# Preliminary_Schematic.net
KiCad netlist of a schematic drawn in EAGLE
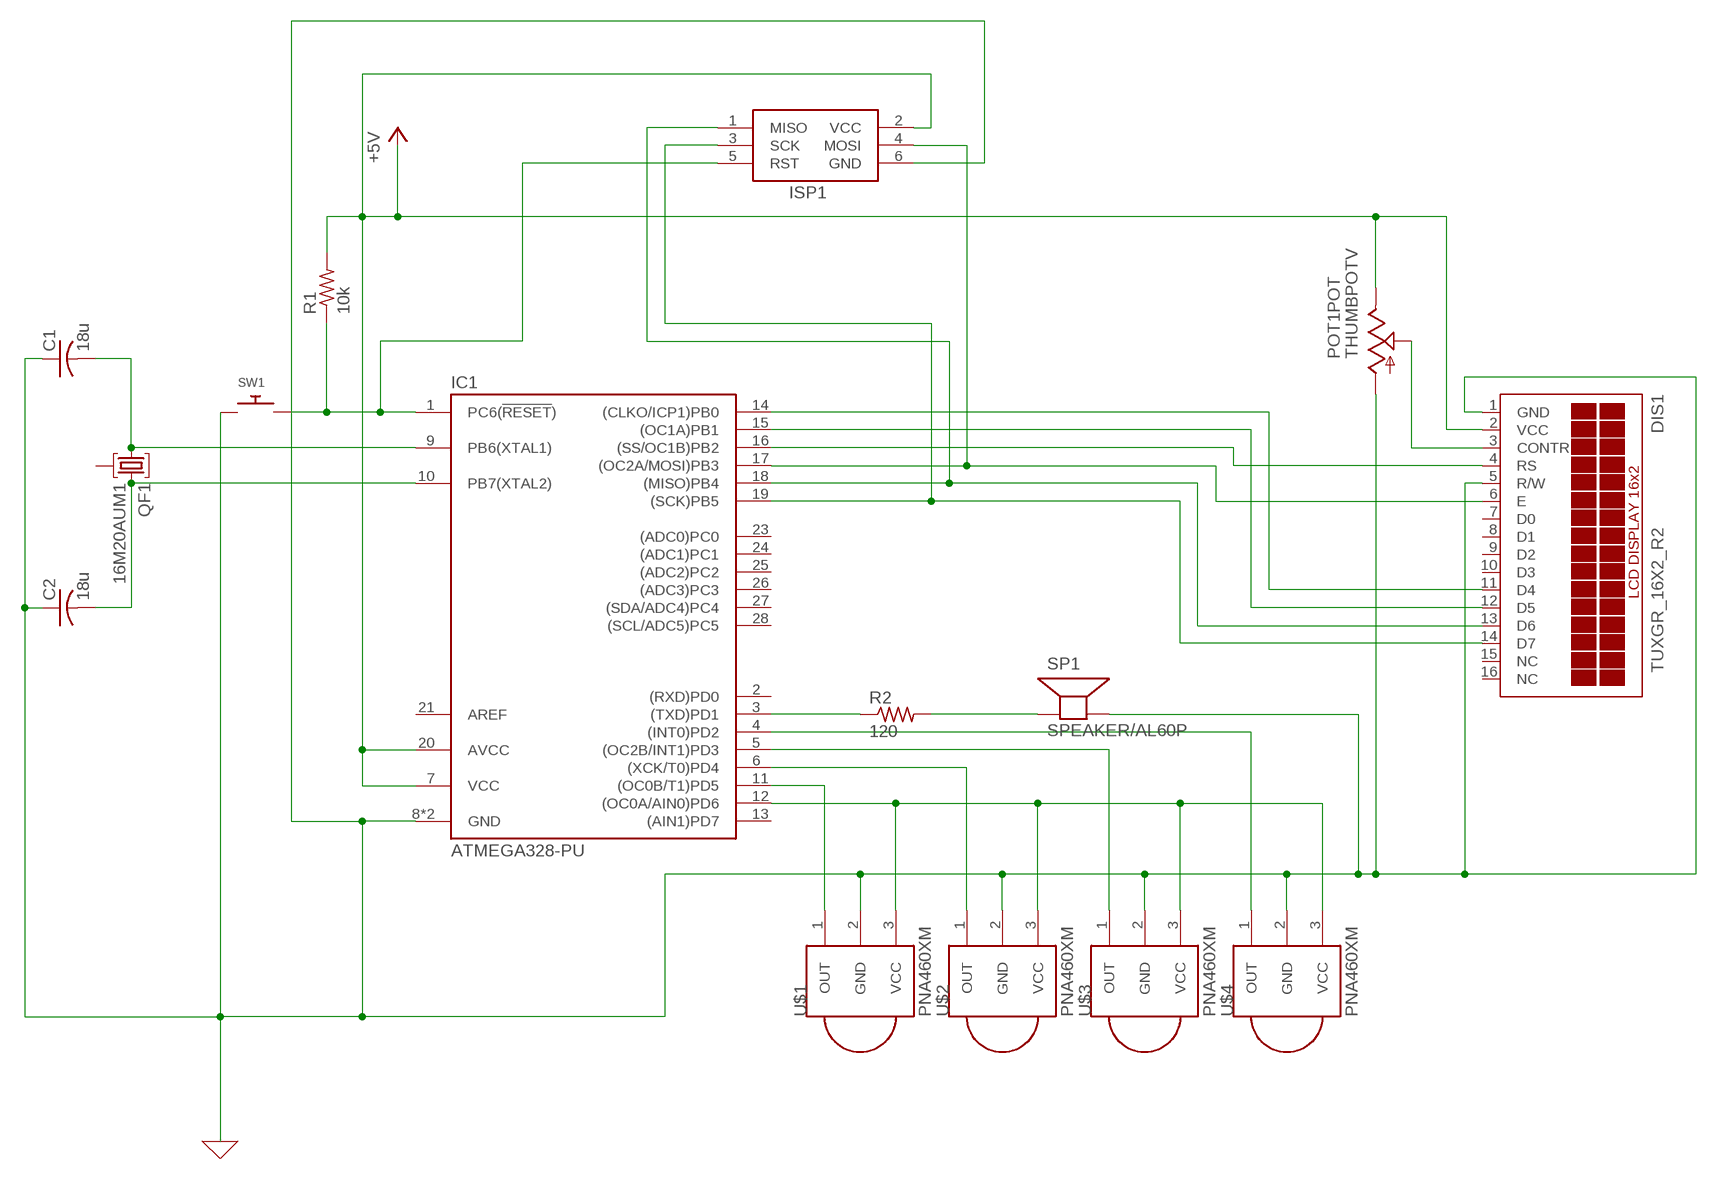
[diagram p0: schematic, sheet 1]

(export (version "E")
  (design (tool "Eeschema 10.0.6"))
  (components
    (comp (ref "C1")
      (value "18u")
      (footprint "eagle-import:C0805")
      (libsource (lib "eagle-import") (part "C-USC0805"))
    )
    (comp (ref "C2")
      (value "18u")
      (footprint "eagle-import:C0805")
      (libsource (lib "eagle-import") (part "C-USC0805"))
    )
    (comp (ref "DIS1")
      (value "TUXGR_16X2_R2")
      (footprint "eagle-import:TUXGR_16X2_R2")
      (libsource (lib "eagle-import") (part "TUXGR_16X2_R2"))
    )
    (comp (ref "IC1")
      (value "ATMEGA328-PU")
      (footprint "eagle-import:DIL28")
      (fields (field (name "MF") "Microchip"))
      (libsource (lib "eagle-import") (part "ATMEGA328-PU"))
    )
    (comp (ref "ISP1")
      (value "AVRISP-6")
      (footprint "eagle-import:AVRISP")
      (libsource (lib "eagle-import") (part "AVRISP-6"))
    )
    (comp (ref "POT1")
      (value "THUMBPOTV")
      (footprint "eagle-import:THUMBWHEELV")
      (libsource (lib "eagle-import") (part "THUMBPOTV"))
    )
    (comp (ref "QF1")
      (value "16M20AUM1")
      (footprint "eagle-import:UM1")
      (libsource (lib "eagle-import") (part "16M20AUM1"))
    )
    (comp (ref "R1")
      (value "10k")
      (footprint "eagle-import:R0805")
      (libsource (lib "eagle-import") (part "R-US_R0805"))
    )
    (comp (ref "R2")
      (value "120")
      (footprint "eagle-import:R0805")
      (libsource (lib "eagle-import") (part "R-US_R0805"))
    )
    (comp (ref "SP1")
      (value "SPEAKER/AL60P")
      (footprint "eagle-import:AL60P")
      (libsource (lib "eagle-import") (part "SPEAKER/AL60P"))
    )
    (comp (ref "SW1")
      (value "SWITCH_PUSHBUTTONC&K_KSS")
      (footprint "eagle-import:BTN_CK_KSS")
      (libsource (lib "eagle-import") (part "SWITCH_PUSHBUTTONC&K_KSS"))
    )
    (comp (ref "U$1")
      (value "PNA460XM")
      (footprint "eagle-import:PNA460XM")
      (libsource (lib "eagle-import") (part "PNA460XM"))
    )
    (comp (ref "U$2")
      (value "PNA460XM")
      (footprint "eagle-import:PNA460XM")
      (libsource (lib "eagle-import") (part "PNA460XM"))
    )
    (comp (ref "U$3")
      (value "PNA460XM")
      (footprint "eagle-import:PNA460XM")
      (libsource (lib "eagle-import") (part "PNA460XM"))
    )
    (comp (ref "U$4")
      (value "PNA460XM")
      (footprint "eagle-import:PNA460XM")
      (libsource (lib "eagle-import") (part "PNA460XM"))
    )
  )
  (nets
    (net (code "1") (name "+5V") (class "Default")
      (node (ref "DIS1") (pin "2") (pinfunction "VCC_2") (pintype "power_in"))
      (node (ref "IC1") (pin "20") (pinfunction "AVCC_20") (pintype "power_in"))
      (node (ref "IC1") (pin "7") (pinfunction "VCC_7") (pintype "power_in"))
      (node (ref "ISP1") (pin "2") (pinfunction "VCC_2") (pintype "power_in"))
      (node (ref "POT1") (pin "E") (pinfunction "E_E") (pintype "passive"))
      (node (ref "R1") (pin "2") (pinfunction "2_2") (pintype "passive"))
    )
    (net (code "2") (name "GND") (class "Default")
      (node (ref "C1") (pin "1") (pinfunction "1_1") (pintype "passive"))
      (node (ref "C2") (pin "1") (pinfunction "1_1") (pintype "passive"))
      (node (ref "DIS1") (pin "1") (pinfunction "GND_1") (pintype "power_in"))
      (node (ref "DIS1") (pin "5") (pinfunction "R/W_5") (pintype "input"))
      (node (ref "IC1") (pin "22") (pinfunction "GND_22") (pintype "power_in"))
      (node (ref "IC1") (pin "8") (pinfunction "GND_8") (pintype "power_in"))
      (node (ref "ISP1") (pin "6") (pinfunction "GND_6") (pintype "power_in"))
      (node (ref "POT1") (pin "A") (pinfunction "A_A") (pintype "passive"))
      (node (ref "SP1") (pin "2") (pinfunction "-_2") (pintype "passive"))
      (node (ref "SW1") (pin "P$1") (pinfunction "P$1_P$1") (pintype "passive"))
      (node (ref "U$1") (pin "2") (pinfunction "GND_2") (pintype "power_in"))
      (node (ref "U$2") (pin "2") (pinfunction "GND_2") (pintype "power_in"))
      (node (ref "U$3") (pin "2") (pinfunction "GND_2") (pintype "power_in"))
      (node (ref "U$4") (pin "2") (pinfunction "GND_2") (pintype "power_in"))
    )
    (net (code "3") (name "Net-(DIS1-CONTR)") (class "Default")
      (node (ref "DIS1") (pin "3") (pinfunction "CONTR_3") (pintype "input"))
      (node (ref "POT1") (pin "S") (pinfunction "S_S") (pintype "passive"))
    )
    (net (code "4") (name "Net-(DIS1-D4)") (class "Default")
      (node (ref "DIS1") (pin "11") (pinfunction "D4_11") (pintype "input"))
      (node (ref "IC1") (pin "14") (pinfunction "(CLKO/ICP1)PB0_14") (pintype "bidirectional"))
    )
    (net (code "5") (name "Net-(DIS1-D5)") (class "Default")
      (node (ref "DIS1") (pin "12") (pinfunction "D5_12") (pintype "input"))
      (node (ref "IC1") (pin "15") (pinfunction "(OC1A)PB1_15") (pintype "bidirectional"))
    )
    (net (code "6") (name "Net-(DIS1-D6)") (class "Default")
      (node (ref "DIS1") (pin "13") (pinfunction "D6_13") (pintype "input"))
      (node (ref "IC1") (pin "18") (pinfunction "(MISO)PB4_18") (pintype "bidirectional"))
      (node (ref "ISP1") (pin "1") (pinfunction "MISO_1") (pintype "input"))
    )
    (net (code "7") (name "Net-(DIS1-D7)") (class "Default")
      (node (ref "DIS1") (pin "14") (pinfunction "D7_14") (pintype "input"))
      (node (ref "IC1") (pin "19") (pinfunction "(SCK)PB5_19") (pintype "bidirectional"))
      (node (ref "ISP1") (pin "3") (pinfunction "SCK_3") (pintype "output"))
    )
    (net (code "8") (name "Net-(DIS1-E)") (class "Default")
      (node (ref "DIS1") (pin "6") (pinfunction "E_6") (pintype "input"))
      (node (ref "IC1") (pin "17") (pinfunction "(OC2A/MOSI)PB3_17") (pintype "bidirectional"))
      (node (ref "ISP1") (pin "4") (pinfunction "MOSI_4") (pintype "output"))
    )
    (net (code "9") (name "Net-(DIS1-RS)") (class "Default")
      (node (ref "DIS1") (pin "4") (pinfunction "RS_4") (pintype "input"))
      (node (ref "IC1") (pin "16") (pinfunction "(SS/OC1B)PB2_16") (pintype "bidirectional"))
    )
    (net (code "10") (name "Net-(IC1-(INT0)PD2)") (class "Default")
      (node (ref "IC1") (pin "4") (pinfunction "(INT0)PD2_4") (pintype "bidirectional"))
      (node (ref "U$4") (pin "1") (pinfunction "OUT_1") (pintype "output"))
    )
    (net (code "11") (name "Net-(IC1-(OC0A{slash}AIN0)PD6)") (class "Default")
      (node (ref "IC1") (pin "12") (pinfunction "(OC0A/AIN0)PD6_12") (pintype "bidirectional"))
      (node (ref "U$1") (pin "3") (pinfunction "VCC_3") (pintype "power_in"))
      (node (ref "U$2") (pin "3") (pinfunction "VCC_3") (pintype "power_in"))
      (node (ref "U$3") (pin "3") (pinfunction "VCC_3") (pintype "power_in"))
      (node (ref "U$4") (pin "3") (pinfunction "VCC_3") (pintype "power_in"))
    )
    (net (code "12") (name "Net-(IC1-(OC0B{slash}T1)PD5)") (class "Default")
      (node (ref "IC1") (pin "11") (pinfunction "(OC0B/T1)PD5_11") (pintype "bidirectional"))
      (node (ref "U$1") (pin "1") (pinfunction "OUT_1") (pintype "output"))
    )
    (net (code "13") (name "Net-(IC1-(OC2B{slash}INT1)PD3)") (class "Default")
      (node (ref "IC1") (pin "5") (pinfunction "(OC2B/INT1)PD3_5") (pintype "bidirectional"))
      (node (ref "U$3") (pin "1") (pinfunction "OUT_1") (pintype "output"))
    )
    (net (code "14") (name "Net-(IC1-(TXD)PD1)") (class "Default")
      (node (ref "IC1") (pin "3") (pinfunction "(TXD)PD1_3") (pintype "bidirectional"))
      (node (ref "R2") (pin "1") (pinfunction "1_1") (pintype "passive"))
    )
    (net (code "15") (name "Net-(IC1-(XCK{slash}T0)PD4)") (class "Default")
      (node (ref "IC1") (pin "6") (pinfunction "(XCK/T0)PD4_6") (pintype "bidirectional"))
      (node (ref "U$2") (pin "1") (pinfunction "OUT_1") (pintype "output"))
    )
    (net (code "16") (name "Net-(IC1-PB6(XTAL1))") (class "Default")
      (node (ref "C1") (pin "2") (pinfunction "2_2") (pintype "passive"))
      (node (ref "IC1") (pin "9") (pinfunction "PB6(XTAL1)_9") (pintype "bidirectional"))
      (node (ref "QF1") (pin "1") (pinfunction "1_1") (pintype "passive"))
    )
    (net (code "17") (name "Net-(IC1-PB7(XTAL2))") (class "Default")
      (node (ref "C2") (pin "2") (pinfunction "2_2") (pintype "passive"))
      (node (ref "IC1") (pin "10") (pinfunction "PB7(XTAL2)_10") (pintype "bidirectional"))
      (node (ref "QF1") (pin "3") (pinfunction "3_3") (pintype "passive"))
    )
    (net (code "18") (name "Net-(IC1-PC6(~{RESET}))") (class "Default")
      (node (ref "IC1") (pin "1") (pinfunction "PC6(~{RESET})_1") (pintype "bidirectional"))
      (node (ref "ISP1") (pin "5") (pinfunction "RST_5") (pintype "output"))
      (node (ref "R1") (pin "1") (pinfunction "1_1") (pintype "passive"))
      (node (ref "SW1") (pin "P$2") (pinfunction "P$2_P$2") (pintype "passive"))
    )
    (net (code "19") (name "Net-(SP1-+)") (class "Default")
      (node (ref "R2") (pin "2") (pinfunction "2_2") (pintype "passive"))
      (node (ref "SP1") (pin "1") (pinfunction "+_1") (pintype "passive"))
    )
    (net (code "20") (name "unconnected-(DIS1-D0-Pad7)") (class "Default")
      (node (ref "DIS1") (pin "7") (pinfunction "D0_7") (pintype "input"))
    )
    (net (code "21") (name "unconnected-(DIS1-D1-Pad8)") (class "Default")
      (node (ref "DIS1") (pin "8") (pinfunction "D1_8") (pintype "input"))
    )
    (net (code "22") (name "unconnected-(DIS1-D2-Pad9)") (class "Default")
      (node (ref "DIS1") (pin "9") (pinfunction "D2_9") (pintype "input"))
    )
    (net (code "23") (name "unconnected-(DIS1-D3-Pad10)") (class "Default")
      (node (ref "DIS1") (pin "10") (pinfunction "D3_10") (pintype "input"))
    )
    (net (code "24") (name "unconnected-(DIS1-NC-Pad15)") (class "Default")
      (node (ref "DIS1") (pin "15") (pinfunction "NC_15") (pintype "no_connect"))
    )
    (net (code "25") (name "unconnected-(DIS1-NC-Pad16)") (class "Default")
      (node (ref "DIS1") (pin "16") (pinfunction "NC_16") (pintype "no_connect"))
    )
    (net (code "26") (name "unconnected-(IC1-(ADC0)PC0-Pad23)") (class "Default")
      (node (ref "IC1") (pin "23") (pinfunction "(ADC0)PC0_23") (pintype "bidirectional"))
    )
    (net (code "27") (name "unconnected-(IC1-(ADC1)PC1-Pad24)") (class "Default")
      (node (ref "IC1") (pin "24") (pinfunction "(ADC1)PC1_24") (pintype "bidirectional"))
    )
    (net (code "28") (name "unconnected-(IC1-(ADC2)PC2-Pad25)") (class "Default")
      (node (ref "IC1") (pin "25") (pinfunction "(ADC2)PC2_25") (pintype "bidirectional"))
    )
    (net (code "29") (name "unconnected-(IC1-(ADC3)PC3-Pad26)") (class "Default")
      (node (ref "IC1") (pin "26") (pinfunction "(ADC3)PC3_26") (pintype "bidirectional"))
    )
    (net (code "30") (name "unconnected-(IC1-(AIN1)PD7-Pad13)") (class "Default")
      (node (ref "IC1") (pin "13") (pinfunction "(AIN1)PD7_13") (pintype "bidirectional"))
    )
    (net (code "31") (name "unconnected-(IC1-(RXD)PD0-Pad2)") (class "Default")
      (node (ref "IC1") (pin "2") (pinfunction "(RXD)PD0_2") (pintype "bidirectional"))
    )
    (net (code "32") (name "unconnected-(IC1-(SCL{slash}ADC5)PC5-Pad28)") (class "Default")
      (node (ref "IC1") (pin "28") (pinfunction "(SCL/ADC5)PC5_28") (pintype "bidirectional"))
    )
    (net (code "33") (name "unconnected-(IC1-(SDA{slash}ADC4)PC4-Pad27)") (class "Default")
      (node (ref "IC1") (pin "27") (pinfunction "(SDA/ADC4)PC4_27") (pintype "bidirectional"))
    )
    (net (code "34") (name "unconnected-(IC1-AREF-Pad21)") (class "Default")
      (node (ref "IC1") (pin "21") (pinfunction "AREF_21") (pintype "passive"))
    )
    (net (code "35") (name "unconnected-(QF1-Pad2)") (class "Default")
      (node (ref "QF1") (pin "2") (pinfunction "2_2") (pintype "passive"))
    )
  )
)
